# BMS_Rev1.net
KiCad netlist of a schematic drawn in EAGLE
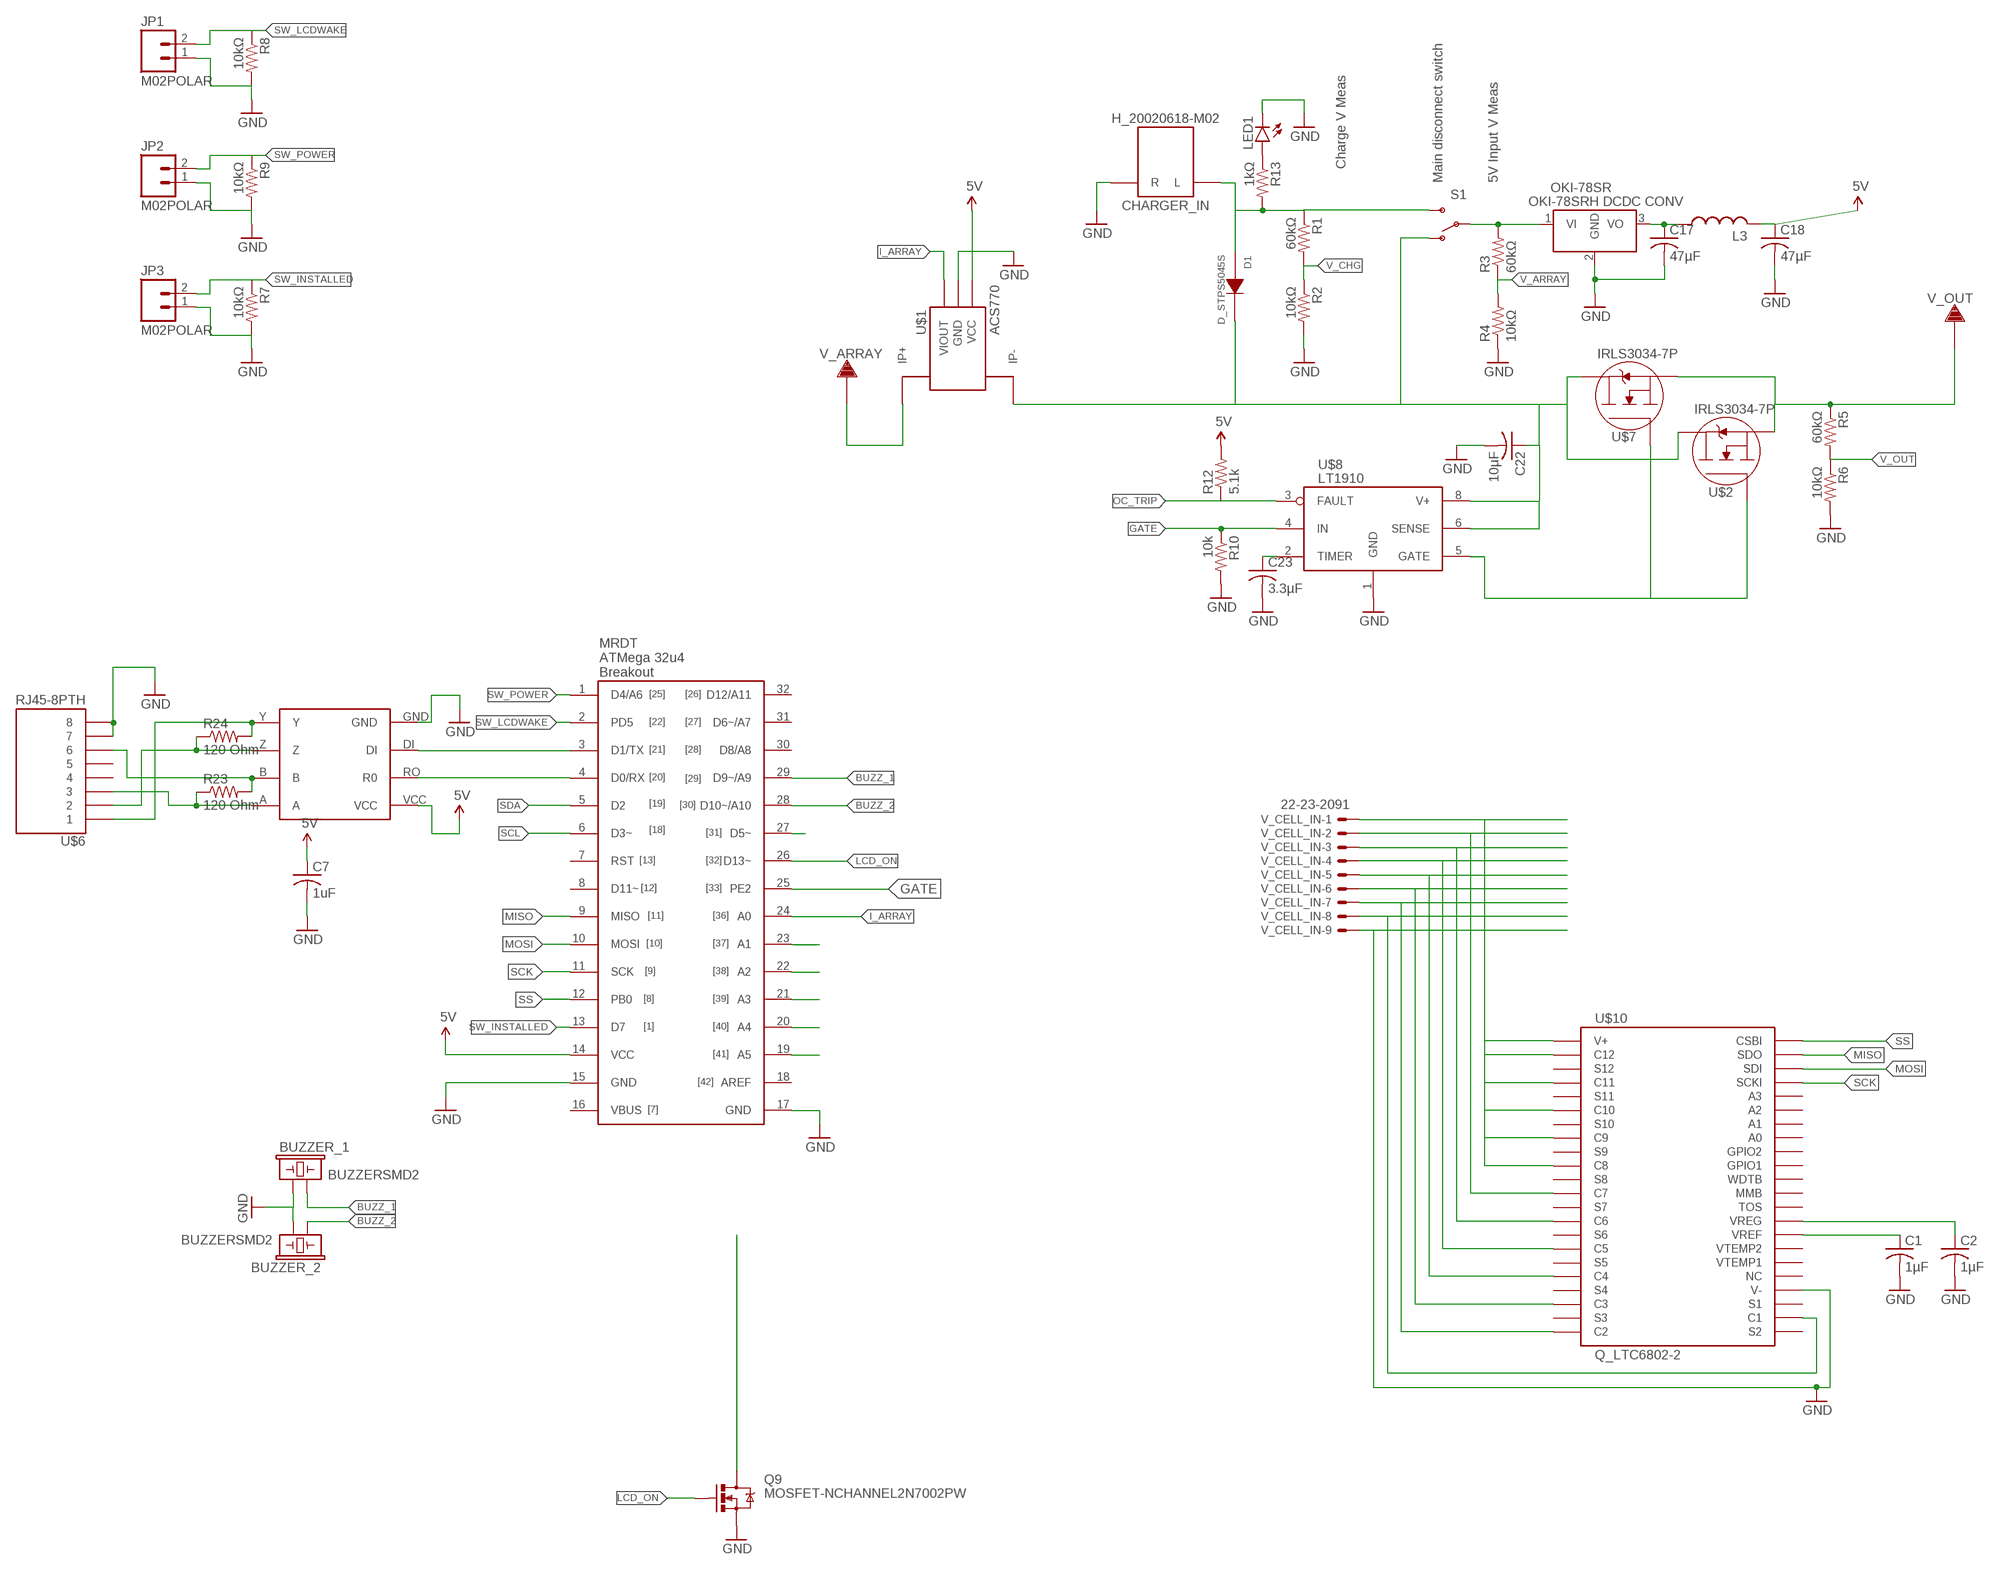
[diagram p0: schematic, sheet 1]

(export (version "E")
  (design (tool "Eeschema 10.0.6"))
  (components
    (comp (ref "BUZZER_1")
      (value "BUZZERSMD2")
      (footprint "eagle-import:BUZZER-CCV")
      (libsource (lib "eagle-import") (part "BUZZERSMD2"))
    )
    (comp (ref "BUZZER_2")
      (value "BUZZERSMD2")
      (footprint "eagle-import:BUZZER-CCV")
      (libsource (lib "eagle-import") (part "BUZZERSMD2"))
    )
    (comp (ref "C1")
      (value "1µF")
      (footprint "eagle-import:C1206")
      (libsource (lib "eagle-import") (part "C-USC1206"))
    )
    (comp (ref "C2")
      (value "1µF")
      (footprint "eagle-import:C1206")
      (libsource (lib "eagle-import") (part "C-USC1206"))
    )
    (comp (ref "C7")
      (value "1uF")
      (footprint "eagle-import:C1206")
      (libsource (lib "eagle-import") (part "C-USC1206"))
    )
    (comp (ref "C17")
      (value "47µF")
      (footprint "eagle-import:C1206")
      (libsource (lib "eagle-import") (part "C-USC1206"))
    )
    (comp (ref "C18")
      (value "47µF")
      (footprint "eagle-import:C1206")
      (libsource (lib "eagle-import") (part "C-USC1206"))
    )
    (comp (ref "C22")
      (value "10µF")
      (footprint "eagle-import:C1206")
      (libsource (lib "eagle-import") (part "C-USC1206"))
    )
    (comp (ref "C23")
      (value "3.3µF")
      (footprint "eagle-import:C1206")
      (libsource (lib "eagle-import") (part "C-USC1206"))
    )
    (comp (ref "CHARGER_IN")
      (value "H_20020618-M02")
      (footprint "eagle-import:20020618-M02")
      (libsource (lib "eagle-import") (part "H_20020618-M02"))
    )
    (comp (ref "D1")
      (value "D_STPS5045S")
      (footprint "eagle-import:D2PACK")
      (libsource (lib "eagle-import") (part "D_STPS5045S"))
    )
    (comp (ref "JP1")
      (value "M02POLAR")
      (footprint "eagle-import:MOLEX-1X2")
      (libsource (lib "eagle-import") (part "M02POLAR"))
    )
    (comp (ref "JP2")
      (value "M02POLAR")
      (footprint "eagle-import:MOLEX-1X2")
      (libsource (lib "eagle-import") (part "M02POLAR"))
    )
    (comp (ref "JP3")
      (value "M02POLAR")
      (footprint "eagle-import:MOLEX-1X2")
      (libsource (lib "eagle-import") (part "M02POLAR"))
    )
    (comp (ref "L3")
      (value "L-USL3216C")
      (footprint "eagle-import:L3216C")
      (libsource (lib "eagle-import") (part "L-USL3216C"))
    )
    (comp (ref "LED1")
      (value "LED1206")
      (footprint "eagle-import:LED-1206")
      (libsource (lib "eagle-import") (part "LED1206"))
    )
    (comp (ref "OKI-78SR")
      (value "Q_OKI-78SR")
      (footprint "eagle-import:OKI-78SRH")
      (libsource (lib "eagle-import") (part "Q_OKI-78SR"))
    )
    (comp (ref "Q9")
      (value "MOSFET-NCHANNEL2N7002PW")
      (footprint "eagle-import:SOT323")
      (libsource (lib "eagle-import") (part "MOSFET-NCHANNEL2N7002PW"))
    )
    (comp (ref "R1")
      (value "60kΩ")
      (footprint "eagle-import:R1206")
      (libsource (lib "eagle-import") (part "R-US_R1206"))
    )
    (comp (ref "R2")
      (value "10kΩ")
      (footprint "eagle-import:R1206")
      (libsource (lib "eagle-import") (part "R-US_R1206"))
    )
    (comp (ref "R3")
      (value "60kΩ")
      (footprint "eagle-import:R1206")
      (libsource (lib "eagle-import") (part "R-US_R1206"))
    )
    (comp (ref "R4")
      (value "10kΩ")
      (footprint "eagle-import:R1206")
      (libsource (lib "eagle-import") (part "R-US_R1206"))
    )
    (comp (ref "R5")
      (value "60kΩ")
      (footprint "eagle-import:R1206")
      (libsource (lib "eagle-import") (part "R-US_R1206"))
    )
    (comp (ref "R6")
      (value "10kΩ")
      (footprint "eagle-import:R1206")
      (libsource (lib "eagle-import") (part "R-US_R1206"))
    )
    (comp (ref "R7")
      (value "10kΩ")
      (footprint "eagle-import:R1206")
      (libsource (lib "eagle-import") (part "R-US_R1206"))
    )
    (comp (ref "R8")
      (value "10kΩ")
      (footprint "eagle-import:R1206")
      (libsource (lib "eagle-import") (part "R-US_R1206"))
    )
    (comp (ref "R9")
      (value "10kΩ")
      (footprint "eagle-import:R1206")
      (libsource (lib "eagle-import") (part "R-US_R1206"))
    )
    (comp (ref "R10")
      (value "10k")
      (footprint "eagle-import:R1206")
      (libsource (lib "eagle-import") (part "R-US_R1206"))
    )
    (comp (ref "R12")
      (value "5.1k")
      (footprint "eagle-import:R1206")
      (libsource (lib "eagle-import") (part "R-US_R1206"))
    )
    (comp (ref "R13")
      (value "1kΩ")
      (footprint "eagle-import:R1206")
      (libsource (lib "eagle-import") (part "R-US_R1206"))
    )
    (comp (ref "R23")
      (value "120 Ohm")
      (footprint "eagle-import:1206")
      (libsource (lib "eagle-import") (part "RESISTOR1206"))
    )
    (comp (ref "R24")
      (value "120 Ohm")
      (footprint "eagle-import:1206")
      (libsource (lib "eagle-import") (part "RESISTOR1206"))
    )
    (comp (ref "S1")
      (value "SWITCH-SPDTPTH")
      (footprint "eagle-import:SWITCH-SPDT")
      (libsource (lib "eagle-import") (part "SWITCH-SPDTPTH"))
    )
    (comp (ref "U$1")
      (value "ACS770")
      (footprint "eagle-import:PFF_LEADFORM")
      (libsource (lib "eagle-import") (part "ACS770"))
    )
    (comp (ref "U$2")
      (value "IRLS3034-7P")
      (footprint "eagle-import:D2PAK-7")
      (libsource (lib "eagle-import") (part "IRLS3034-7P"))
    )
    (comp (ref "U$3")
      (value "32U4_BREAKOUT")
      (footprint "eagle-import:32U4_MCU_DIP")
      (libsource (lib "eagle-import") (part "32U4_BREAKOUT"))
    )
    (comp (ref "U$6")
      (value "RJ45-8PTH")
      (footprint "eagle-import:RJ45-8")
      (libsource (lib "eagle-import") (part "RJ45-8PTH"))
    )
    (comp (ref "U$7")
      (value "IRLS3034-7P")
      (footprint "eagle-import:D2PAK-7")
      (libsource (lib "eagle-import") (part "IRLS3034-7P"))
    )
    (comp (ref "U$8")
      (value "LT1910")
      (footprint "eagle-import:SO8")
      (libsource (lib "eagle-import") (part "LT1910"))
    )
    (comp (ref "U$9")
      (value "MAX3077")
      (footprint "eagle-import:MAX3070E")
      (libsource (lib "eagle-import") (part "MAX3077"))
    )
    (comp (ref "U$10")
      (value "Q_LTC6802-2")
      (footprint "eagle-import:SSOP44")
      (libsource (lib "eagle-import") (part "Q_LTC6802-2"))
    )
    (comp (ref "V_ARRAY")
      (value "TERMINAL_HOLE")
      (footprint "eagle-import:LARGE_TERMINAL_HOLE")
      (libsource (lib "eagle-import") (part "TERMINAL_HOLE"))
    )
    (comp (ref "V_CELL_IN")
      (value "22-23-2091")
      (footprint "eagle-import:22-23-2091")
      (fields (field (name "MF") "MOLEX"))
      (libsource (lib "eagle-import") (part "22-23-2091"))
    )
    (comp (ref "V_OUT")
      (value "TERMINAL_HOLE")
      (footprint "eagle-import:LARGE_TERMINAL_HOLE")
      (libsource (lib "eagle-import") (part "TERMINAL_HOLE"))
    )
  )
  (nets
    (net (code "1") (name "5V") (class "Default")
      (node (ref "C18") (pin "1") (pinfunction "1_1") (pintype "passive"))
      (node (ref "C7") (pin "1") (pinfunction "1_1") (pintype "passive"))
      (node (ref "L3") (pin "2") (pinfunction "2_2") (pintype "passive"))
      (node (ref "R12") (pin "2") (pinfunction "2_2") (pintype "passive"))
      (node (ref "U$1") (pin "1") (pinfunction "VCC_1") (pintype "bidirectional"))
      (node (ref "U$3") (pin "14") (pinfunction "VCC_14") (pintype "bidirectional"))
      (node (ref "U$9") (pin "VCC") (pinfunction "VCC_VCC") (pintype "bidirectional"))
    )
    (net (code "2") (name "BUZZ_1") (class "Default")
      (node (ref "BUZZER_1") (pin "-") (pinfunction "2_-") (pintype "passive"))
      (node (ref "U$3") (pin "29") (pinfunction "D9~{/A9}_29") (pintype "bidirectional"))
    )
    (net (code "3") (name "BUZZ_2") (class "Default")
      (node (ref "BUZZER_2") (pin "+") (pinfunction "1_+") (pintype "passive"))
      (node (ref "U$3") (pin "28") (pinfunction "D10~{/A10}_28") (pintype "bidirectional"))
    )
    (net (code "4") (name "GATE") (class "Default")
      (node (ref "R10") (pin "1") (pinfunction "1_1") (pintype "passive"))
      (node (ref "U$3") (pin "25") (pinfunction "PE2_25") (pintype "bidirectional"))
      (node (ref "U$8") (pin "4") (pinfunction "IN_4") (pintype "bidirectional"))
    )
    (net (code "5") (name "GND") (class "Default")
      (node (ref "BUZZER_1") (pin "+") (pinfunction "1_+") (pintype "passive"))
      (node (ref "BUZZER_2") (pin "-") (pinfunction "2_-") (pintype "passive"))
      (node (ref "C1") (pin "2") (pinfunction "2_2") (pintype "passive"))
      (node (ref "C17") (pin "2") (pinfunction "2_2") (pintype "passive"))
      (node (ref "C18") (pin "2") (pinfunction "2_2") (pintype "passive"))
      (node (ref "C2") (pin "2") (pinfunction "2_2") (pintype "passive"))
      (node (ref "C22") (pin "2") (pinfunction "2_2") (pintype "passive"))
      (node (ref "C23") (pin "2") (pinfunction "2_2") (pintype "passive"))
      (node (ref "C7") (pin "2") (pinfunction "2_2") (pintype "passive"))
      (node (ref "CHARGER_IN") (pin "R1") (pinfunction "R_R1") (pintype "bidirectional"))
      (node (ref "CHARGER_IN") (pin "R2") (pinfunction "R_R2") (pintype "bidirectional"))
      (node (ref "JP1") (pin "1") (pinfunction "1_1") (pintype "passive"))
      (node (ref "JP2") (pin "1") (pinfunction "1_1") (pintype "passive"))
      (node (ref "JP3") (pin "1") (pinfunction "1_1") (pintype "passive"))
      (node (ref "LED1") (pin "C") (pinfunction "C_C") (pintype "passive"))
      (node (ref "OKI-78SR") (pin "2") (pinfunction "GND_2") (pintype "bidirectional"))
      (node (ref "Q9") (pin "2") (pinfunction "S_2") (pintype "passive"))
      (node (ref "R10") (pin "2") (pinfunction "2_2") (pintype "passive"))
      (node (ref "R2") (pin "2") (pinfunction "2_2") (pintype "passive"))
      (node (ref "R4") (pin "1") (pinfunction "1_1") (pintype "passive"))
      (node (ref "R6") (pin "2") (pinfunction "2_2") (pintype "passive"))
      (node (ref "R7") (pin "2") (pinfunction "2_2") (pintype "passive"))
      (node (ref "R8") (pin "2") (pinfunction "2_2") (pintype "passive"))
      (node (ref "R9") (pin "2") (pinfunction "2_2") (pintype "passive"))
      (node (ref "U$1") (pin "2") (pinfunction "GND_2") (pintype "bidirectional"))
      (node (ref "U$10") (pin "26") (pinfunction "V-_26") (pintype "bidirectional"))
      (node (ref "U$3") (pin "15") (pinfunction "GND_15") (pintype "bidirectional"))
      (node (ref "U$3") (pin "17") (pinfunction "GND_17") (pintype "bidirectional"))
      (node (ref "U$6") (pin "7") (pinfunction "7_7") (pintype "bidirectional"))
      (node (ref "U$6") (pin "8") (pinfunction "8_8") (pintype "bidirectional"))
      (node (ref "U$8") (pin "1") (pinfunction "GND_1") (pintype "bidirectional"))
      (node (ref "U$9") (pin "GND") (pinfunction "GND_GND") (pintype "bidirectional"))
      (node (ref "V_CELL_IN") (pin "9") (pinfunction "S_9") (pintype "passive"))
    )
    (net (code "6") (name "I_ARRAY") (class "Default")
      (node (ref "U$1") (pin "3") (pinfunction "VIOUT_3") (pintype "bidirectional"))
      (node (ref "U$3") (pin "24") (pinfunction "A0_24") (pintype "bidirectional"))
    )
    (net (code "7") (name "LCD_ON") (class "Default")
      (node (ref "Q9") (pin "1") (pinfunction "G_1") (pintype "passive"))
      (node (ref "U$3") (pin "26") (pinfunction "D13~{}_26") (pintype "bidirectional"))
    )
    (net (code "8") (name "MISO") (class "Default")
      (node (ref "U$10") (pin "43") (pinfunction "SDO_43") (pintype "bidirectional"))
      (node (ref "U$3") (pin "9") (pinfunction "MISO_9") (pintype "bidirectional"))
    )
    (net (code "9") (name "MOSI") (class "Default")
      (node (ref "U$10") (pin "42") (pinfunction "SDI_42") (pintype "bidirectional"))
      (node (ref "U$3") (pin "10") (pinfunction "MOSI_10") (pintype "bidirectional"))
    )
    (net (code "10") (name "Net-(D1-K)") (class "Default")
      (node (ref "C22") (pin "1") (pinfunction "1_1") (pintype "passive"))
      (node (ref "D1") (pin "TAB") (pinfunction "K_TAB") (pintype "bidirectional"))
      (node (ref "S1") (pin "1") (pinfunction "O_1") (pintype "passive"))
      (node (ref "U$1") (pin "5_1") (pinfunction "IP-_5_1") (pintype "bidirectional"))
      (node (ref "U$1") (pin "5_10") (pinfunction "IP-_5_10") (pintype "bidirectional"))
      (node (ref "U$1") (pin "5_11") (pinfunction "IP-_5_11") (pintype "bidirectional"))
      (node (ref "U$1") (pin "5_12") (pinfunction "IP-_5_12") (pintype "bidirectional"))
      (node (ref "U$1") (pin "5_13") (pinfunction "IP-_5_13") (pintype "bidirectional"))
      (node (ref "U$1") (pin "5_14") (pinfunction "IP-_5_14") (pintype "bidirectional"))
      (node (ref "U$1") (pin "5_15") (pinfunction "IP-_5_15") (pintype "bidirectional"))
      (node (ref "U$1") (pin "5_16") (pinfunction "IP-_5_16") (pintype "bidirectional"))
      (node (ref "U$1") (pin "5_2") (pinfunction "IP-_5_2") (pintype "bidirectional"))
      (node (ref "U$1") (pin "5_3") (pinfunction "IP-_5_3") (pintype "bidirectional"))
      (node (ref "U$1") (pin "5_4") (pinfunction "IP-_5_4") (pintype "bidirectional"))
      (node (ref "U$1") (pin "5_5") (pinfunction "IP-_5_5") (pintype "bidirectional"))
      (node (ref "U$1") (pin "5_6") (pinfunction "IP-_5_6") (pintype "bidirectional"))
      (node (ref "U$1") (pin "5_7") (pinfunction "IP-_5_7") (pintype "bidirectional"))
      (node (ref "U$1") (pin "5_8") (pinfunction "IP-_5_8") (pintype "bidirectional"))
      (node (ref "U$1") (pin "5_9") (pinfunction "IP-_5_9") (pintype "bidirectional"))
      (node (ref "U$1") (pin "5_B") (pinfunction "IP-_5_B") (pintype "bidirectional"))
      (node (ref "U$1") (pin "5_T") (pinfunction "IP-_5_T") (pintype "bidirectional"))
      (node (ref "U$2") (pin "PAD") (pinfunction "DRAIN_PAD") (pintype "bidirectional"))
      (node (ref "U$7") (pin "PAD") (pinfunction "DRAIN_PAD") (pintype "bidirectional"))
      (node (ref "U$8") (pin "6") (pinfunction "SENSE_6") (pintype "bidirectional"))
      (node (ref "U$8") (pin "8") (pinfunction "V+_8") (pintype "bidirectional"))
    )
    (net (code "11") (name "Net-(LED1-PadA)") (class "Default")
      (node (ref "LED1") (pin "A") (pinfunction "A_A") (pintype "passive"))
      (node (ref "R13") (pin "1") (pinfunction "1_1") (pintype "passive"))
    )
    (net (code "12") (name "Net-(OKI-78SR-VI)") (class "Default")
      (node (ref "OKI-78SR") (pin "1") (pinfunction "VI_1") (pintype "bidirectional"))
      (node (ref "R3") (pin "2") (pinfunction "2_2") (pintype "passive"))
      (node (ref "S1") (pin "2") (pinfunction "P_2") (pintype "passive"))
    )
    (net (code "13") (name "Net-(OKI-78SR-VO)") (class "Default")
      (node (ref "C17") (pin "1") (pinfunction "1_1") (pintype "passive"))
      (node (ref "L3") (pin "1") (pinfunction "1_1") (pintype "passive"))
      (node (ref "OKI-78SR") (pin "3") (pinfunction "VO_3") (pintype "bidirectional"))
    )
    (net (code "14") (name "Net-(R5-Pad1)") (class "Default")
      (node (ref "R5") (pin "1") (pinfunction "1_1") (pintype "passive"))
      (node (ref "U$2") (pin "2") (pinfunction "SOURCE_2") (pintype "bidirectional"))
      (node (ref "U$2") (pin "3") (pinfunction "SOURCE_3") (pintype "bidirectional"))
      (node (ref "U$2") (pin "4") (pinfunction "SOURCE_4") (pintype "bidirectional"))
      (node (ref "U$2") (pin "5") (pinfunction "SOURCE_5") (pintype "bidirectional"))
      (node (ref "U$2") (pin "6") (pinfunction "SOURCE_6") (pintype "bidirectional"))
      (node (ref "U$7") (pin "2") (pinfunction "SOURCE_2") (pintype "bidirectional"))
      (node (ref "U$7") (pin "3") (pinfunction "SOURCE_3") (pintype "bidirectional"))
      (node (ref "U$7") (pin "4") (pinfunction "SOURCE_4") (pintype "bidirectional"))
      (node (ref "U$7") (pin "5") (pinfunction "SOURCE_5") (pintype "bidirectional"))
      (node (ref "U$7") (pin "6") (pinfunction "SOURCE_6") (pintype "bidirectional"))
      (node (ref "V_OUT") (pin "P$1") (pinfunction "P$1_P$1") (pintype "bidirectional"))
    )
    (net (code "15") (name "Net-(R23-Pad1)") (class "Default")
      (node (ref "R23") (pin "1") (pinfunction "1_1") (pintype "passive"))
      (node (ref "U$6") (pin "3") (pinfunction "3_3") (pintype "bidirectional"))
      (node (ref "U$9") (pin "A") (pinfunction "A_A") (pintype "bidirectional"))
    )
    (net (code "16") (name "Net-(R23-Pad2)") (class "Default")
      (node (ref "R23") (pin "2") (pinfunction "2_2") (pintype "passive"))
      (node (ref "U$6") (pin "6") (pinfunction "6_6") (pintype "bidirectional"))
      (node (ref "U$9") (pin "B") (pinfunction "B_B") (pintype "bidirectional"))
    )
    (net (code "17") (name "Net-(R24-Pad1)") (class "Default")
      (node (ref "R24") (pin "1") (pinfunction "1_1") (pintype "passive"))
      (node (ref "U$6") (pin "2") (pinfunction "2_2") (pintype "bidirectional"))
      (node (ref "U$9") (pin "Z") (pinfunction "Z_Z") (pintype "bidirectional"))
    )
    (net (code "18") (name "Net-(R24-Pad2)") (class "Default")
      (node (ref "R24") (pin "2") (pinfunction "2_2") (pintype "passive"))
      (node (ref "U$6") (pin "1") (pinfunction "1_1") (pintype "bidirectional"))
      (node (ref "U$9") (pin "Y") (pinfunction "Y_Y") (pintype "bidirectional"))
    )
    (net (code "19") (name "Net-(S1-S)") (class "Default")
      (node (ref "CHARGER_IN") (pin "L1") (pinfunction "L_L1") (pintype "bidirectional"))
      (node (ref "CHARGER_IN") (pin "L2") (pinfunction "L_L2") (pintype "bidirectional"))
      (node (ref "D1") (pin "1") (pinfunction "A_1") (pintype "bidirectional"))
      (node (ref "D1") (pin "2") (pinfunction "A_2") (pintype "bidirectional"))
      (node (ref "R1") (pin "1") (pinfunction "1_1") (pintype "passive"))
      (node (ref "R13") (pin "2") (pinfunction "2_2") (pintype "passive"))
      (node (ref "S1") (pin "3") (pinfunction "S_3") (pintype "passive"))
    )
    (net (code "20") (name "Net-(U$1-IP+-Pad4_1)") (class "Default")
      (node (ref "U$1") (pin "4_1") (pinfunction "IP+_4_1") (pintype "bidirectional"))
      (node (ref "U$1") (pin "4_10") (pinfunction "IP+_4_10") (pintype "bidirectional"))
      (node (ref "U$1") (pin "4_11") (pinfunction "IP+_4_11") (pintype "bidirectional"))
      (node (ref "U$1") (pin "4_12") (pinfunction "IP+_4_12") (pintype "bidirectional"))
      (node (ref "U$1") (pin "4_13") (pinfunction "IP+_4_13") (pintype "bidirectional"))
      (node (ref "U$1") (pin "4_14") (pinfunction "IP+_4_14") (pintype "bidirectional"))
      (node (ref "U$1") (pin "4_15") (pinfunction "IP+_4_15") (pintype "bidirectional"))
      (node (ref "U$1") (pin "4_16") (pinfunction "IP+_4_16") (pintype "bidirectional"))
      (node (ref "U$1") (pin "4_2") (pinfunction "IP+_4_2") (pintype "bidirectional"))
      (node (ref "U$1") (pin "4_3") (pinfunction "IP+_4_3") (pintype "bidirectional"))
      (node (ref "U$1") (pin "4_4") (pinfunction "IP+_4_4") (pintype "bidirectional"))
      (node (ref "U$1") (pin "4_5") (pinfunction "IP+_4_5") (pintype "bidirectional"))
      (node (ref "U$1") (pin "4_6") (pinfunction "IP+_4_6") (pintype "bidirectional"))
      (node (ref "U$1") (pin "4_7") (pinfunction "IP+_4_7") (pintype "bidirectional"))
      (node (ref "U$1") (pin "4_8") (pinfunction "IP+_4_8") (pintype "bidirectional"))
      (node (ref "U$1") (pin "4_9") (pinfunction "IP+_4_9") (pintype "bidirectional"))
      (node (ref "U$1") (pin "4_B") (pinfunction "IP+_4_B") (pintype "bidirectional"))
      (node (ref "U$1") (pin "4_T") (pinfunction "IP+_4_T") (pintype "bidirectional"))
      (node (ref "V_ARRAY") (pin "P$1") (pinfunction "P$1_P$1") (pintype "bidirectional"))
    )
    (net (code "21") (name "Net-(U$2-GATE)") (class "Default")
      (node (ref "U$2") (pin "1") (pinfunction "GATE_1") (pintype "bidirectional"))
      (node (ref "U$7") (pin "1") (pinfunction "GATE_1") (pintype "bidirectional"))
      (node (ref "U$8") (pin "5") (pinfunction "GATE_5") (pintype "bidirectional"))
    )
    (net (code "22") (name "Net-(U$3-D0{slash}RX)") (class "Default")
      (node (ref "U$3") (pin "4") (pinfunction "D0/RX_4") (pintype "bidirectional"))
      (node (ref "U$9") (pin "RO") (pinfunction "R0_RO") (pintype "bidirectional"))
    )
    (net (code "23") (name "Net-(U$3-D1{slash}TX)") (class "Default")
      (node (ref "U$3") (pin "3") (pinfunction "D1/TX_3") (pintype "bidirectional"))
      (node (ref "U$9") (pin "DI") (pinfunction "DI_DI") (pintype "bidirectional"))
    )
    (net (code "24") (name "Net-(U$8-TIMER)") (class "Default")
      (node (ref "C23") (pin "1") (pinfunction "1_1") (pintype "passive"))
      (node (ref "U$8") (pin "2") (pinfunction "TIMER_2") (pintype "bidirectional"))
    )
    (net (code "25") (name "Net-(U$10-C1)") (class "Default")
      (node (ref "U$10") (pin "24") (pinfunction "C1_24") (pintype "bidirectional"))
      (node (ref "V_CELL_IN") (pin "8") (pinfunction "S_8") (pintype "passive"))
    )
    (net (code "26") (name "Net-(U$10-C2)") (class "Default")
      (node (ref "U$10") (pin "22") (pinfunction "C2_22") (pintype "bidirectional"))
      (node (ref "V_CELL_IN") (pin "7") (pinfunction "S_7") (pintype "passive"))
    )
    (net (code "27") (name "Net-(U$10-C3)") (class "Default")
      (node (ref "U$10") (pin "20") (pinfunction "C3_20") (pintype "bidirectional"))
      (node (ref "V_CELL_IN") (pin "6") (pinfunction "S_6") (pintype "passive"))
    )
    (net (code "28") (name "Net-(U$10-C4)") (class "Default")
      (node (ref "U$10") (pin "18") (pinfunction "C4_18") (pintype "bidirectional"))
      (node (ref "V_CELL_IN") (pin "5") (pinfunction "S_5") (pintype "passive"))
    )
    (net (code "29") (name "Net-(U$10-C5)") (class "Default")
      (node (ref "U$10") (pin "16") (pinfunction "C5_16") (pintype "bidirectional"))
      (node (ref "V_CELL_IN") (pin "4") (pinfunction "S_4") (pintype "passive"))
    )
    (net (code "30") (name "Net-(U$10-C6)") (class "Default")
      (node (ref "U$10") (pin "14") (pinfunction "C6_14") (pintype "bidirectional"))
      (node (ref "V_CELL_IN") (pin "3") (pinfunction "S_3") (pintype "passive"))
    )
    (net (code "31") (name "Net-(U$10-C7)") (class "Default")
      (node (ref "U$10") (pin "12") (pinfunction "C7_12") (pintype "bidirectional"))
      (node (ref "V_CELL_IN") (pin "2") (pinfunction "S_2") (pintype "passive"))
    )
    (net (code "32") (name "Net-(U$10-C10)") (class "Default")
      (node (ref "U$10") (pin "1") (pinfunction "V+_1") (pintype "bidirectional"))
      (node (ref "U$10") (pin "10") (pinfunction "C8_10") (pintype "bidirectional"))
      (node (ref "U$10") (pin "2") (pinfunction "C12_2") (pintype "bidirectional"))
      (node (ref "U$10") (pin "4") (pinfunction "C11_4") (pintype "bidirectional"))
      (node (ref "U$10") (pin "6") (pinfunction "C10_6") (pintype "bidirectional"))
      (node (ref "U$10") (pin "8") (pinfunction "C9_8") (pintype "bidirectional"))
      (node (ref "V_CELL_IN") (pin "1") (pinfunction "S_1") (pintype "passive"))
    )
    (net (code "33") (name "Net-(U$10-VREF)") (class "Default")
      (node (ref "C1") (pin "1") (pinfunction "1_1") (pintype "passive"))
      (node (ref "U$10") (pin "30") (pinfunction "VREF_30") (pintype "bidirectional"))
    )
    (net (code "34") (name "Net-(U$10-VREG)") (class "Default")
      (node (ref "C2") (pin "1") (pinfunction "1_1") (pintype "passive"))
      (node (ref "U$10") (pin "31") (pinfunction "VREG_31") (pintype "bidirectional"))
    )
    (net (code "35") (name "OC_TRIP") (class "Default")
      (node (ref "R12") (pin "1") (pinfunction "1_1") (pintype "passive"))
      (node (ref "U$8") (pin "3") (pinfunction "FAULT_3") (pintype "bidirectional"))
    )
    (net (code "36") (name "SCK") (class "Default")
      (node (ref "U$10") (pin "41") (pinfunction "SCKI_41") (pintype "bidirectional"))
      (node (ref "U$3") (pin "11") (pinfunction "SCK_11") (pintype "bidirectional"))
    )
    (net (code "37") (name "SCL") (class "Default")
      (node (ref "U$3") (pin "6") (pinfunction "D3~{}_6") (pintype "bidirectional"))
    )
    (net (code "38") (name "SDA") (class "Default")
      (node (ref "U$3") (pin "5") (pinfunction "D2_5") (pintype "bidirectional"))
    )
    (net (code "39") (name "SS") (class "Default")
      (node (ref "U$10") (pin "44") (pinfunction "CSBI_44") (pintype "bidirectional"))
      (node (ref "U$3") (pin "12") (pinfunction "PB0_12") (pintype "bidirectional"))
    )
    (net (code "40") (name "SW_INSTALLED") (class "Default")
      (node (ref "JP3") (pin "2") (pinfunction "2_2") (pintype "passive"))
      (node (ref "R7") (pin "1") (pinfunction "1_1") (pintype "passive"))
      (node (ref "U$3") (pin "13") (pinfunction "D7_13") (pintype "bidirectional"))
    )
    (net (code "41") (name "SW_LCDWAKE") (class "Default")
      (node (ref "JP1") (pin "2") (pinfunction "2_2") (pintype "passive"))
      (node (ref "R8") (pin "1") (pinfunction "1_1") (pintype "passive"))
      (node (ref "U$3") (pin "2") (pinfunction "PD5_2") (pintype "bidirectional"))
    )
    (net (code "42") (name "SW_POWER") (class "Default")
      (node (ref "JP2") (pin "2") (pinfunction "2_2") (pintype "passive"))
      (node (ref "R9") (pin "1") (pinfunction "1_1") (pintype "passive"))
      (node (ref "U$3") (pin "1") (pinfunction "D4/A6_1") (pintype "bidirectional"))
    )
    (net (code "43") (name "V_ARRAY") (class "Default")
      (node (ref "R3") (pin "1") (pinfunction "1_1") (pintype "passive"))
      (node (ref "R4") (pin "2") (pinfunction "2_2") (pintype "passive"))
    )
    (net (code "44") (name "V_CHG") (class "Default")
      (node (ref "R1") (pin "2") (pinfunction "2_2") (pintype "passive"))
      (node (ref "R2") (pin "1") (pinfunction "1_1") (pintype "passive"))
    )
    (net (code "45") (name "V_OUT") (class "Default")
      (node (ref "R5") (pin "2") (pinfunction "2_2") (pintype "passive"))
      (node (ref "R6") (pin "1") (pinfunction "1_1") (pintype "passive"))
    )
    (net (code "46") (name "unconnected-(Q9-D-Pad3)") (class "Default")
      (node (ref "Q9") (pin "3") (pinfunction "D_3") (pintype "passive"))
    )
    (net (code "47") (name "unconnected-(U$3-A1-Pad23)") (class "Default")
      (node (ref "U$3") (pin "23") (pinfunction "A1_23") (pintype "bidirectional"))
    )
    (net (code "48") (name "unconnected-(U$3-A2-Pad22)") (class "Default")
      (node (ref "U$3") (pin "22") (pinfunction "A2_22") (pintype "bidirectional"))
    )
    (net (code "49") (name "unconnected-(U$3-A3-Pad21)") (class "Default")
      (node (ref "U$3") (pin "21") (pinfunction "A3_21") (pintype "bidirectional"))
    )
    (net (code "50") (name "unconnected-(U$3-A4-Pad20)") (class "Default")
      (node (ref "U$3") (pin "20") (pinfunction "A4_20") (pintype "bidirectional"))
    )
    (net (code "51") (name "unconnected-(U$3-A5-Pad19)") (class "Default")
      (node (ref "U$3") (pin "19") (pinfunction "A5_19") (pintype "bidirectional"))
    )
    (net (code "52") (name "unconnected-(U$3-AREF-Pad18)") (class "Default")
      (node (ref "U$3") (pin "18") (pinfunction "AREF_18") (pintype "bidirectional"))
    )
    (net (code "53") (name "unconnected-(U$3-D5~{}-Pad27)") (class "Default")
      (node (ref "U$3") (pin "27") (pinfunction "D5~{}_27") (pintype "bidirectional"))
    )
    (net (code "54") (name "unconnected-(U$3-D6~{{slash}A7}-Pad31)") (class "Default")
      (node (ref "U$3") (pin "31") (pinfunction "D6~{/A7}_31") (pintype "bidirectional"))
    )
    (net (code "55") (name "unconnected-(U$3-D8{slash}A8-Pad30)") (class "Default")
      (node (ref "U$3") (pin "30") (pinfunction "D8/A8_30") (pintype "bidirectional"))
    )
    (net (code "56") (name "unconnected-(U$3-D11~{}-Pad8)") (class "Default")
      (node (ref "U$3") (pin "8") (pinfunction "D11~{}_8") (pintype "bidirectional"))
    )
    (net (code "57") (name "unconnected-(U$3-D12{slash}A11-Pad32)") (class "Default")
      (node (ref "U$3") (pin "32") (pinfunction "D12/A11_32") (pintype "bidirectional"))
    )
    (net (code "58") (name "unconnected-(U$3-RST-Pad7)") (class "Default")
      (node (ref "U$3") (pin "7") (pinfunction "RST_7") (pintype "bidirectional"))
    )
    (net (code "59") (name "unconnected-(U$3-VBUS-Pad16)") (class "Default")
      (node (ref "U$3") (pin "16") (pinfunction "VBUS_16") (pintype "bidirectional"))
    )
    (net (code "60") (name "unconnected-(U$6-Pad4)") (class "Default")
      (node (ref "U$6") (pin "4") (pinfunction "4_4") (pintype "bidirectional"))
    )
    (net (code "61") (name "unconnected-(U$6-Pad5)") (class "Default")
      (node (ref "U$6") (pin "5") (pinfunction "5_5") (pintype "bidirectional"))
    )
    (net (code "62") (name "unconnected-(U$10-A0-Pad37)") (class "Default")
      (node (ref "U$10") (pin "37") (pinfunction "A0_37") (pintype "bidirectional"))
    )
    (net (code "63") (name "unconnected-(U$10-A1-Pad38)") (class "Default")
      (node (ref "U$10") (pin "38") (pinfunction "A1_38") (pintype "bidirectional"))
    )
    (net (code "64") (name "unconnected-(U$10-A2-Pad39)") (class "Default")
      (node (ref "U$10") (pin "39") (pinfunction "A2_39") (pintype "bidirectional"))
    )
    (net (code "65") (name "unconnected-(U$10-A3-Pad40)") (class "Default")
      (node (ref "U$10") (pin "40") (pinfunction "A3_40") (pintype "bidirectional"))
    )
    (net (code "66") (name "unconnected-(U$10-GPIO1-Pad35)") (class "Default")
      (node (ref "U$10") (pin "35") (pinfunction "GPIO1_35") (pintype "bidirectional"))
    )
    (net (code "67") (name "unconnected-(U$10-GPIO2-Pad36)") (class "Default")
      (node (ref "U$10") (pin "36") (pinfunction "GPIO2_36") (pintype "bidirectional"))
    )
    (net (code "68") (name "unconnected-(U$10-MMB-Pad33)") (class "Default")
      (node (ref "U$10") (pin "33") (pinfunction "MMB_33") (pintype "bidirectional"))
    )
    (net (code "69") (name "unconnected-(U$10-NC-Pad27)") (class "Default")
      (node (ref "U$10") (pin "27") (pinfunction "NC_27") (pintype "bidirectional"))
    )
    (net (code "70") (name "unconnected-(U$10-S1-Pad25)") (class "Default")
      (node (ref "U$10") (pin "25") (pinfunction "S1_25") (pintype "bidirectional"))
    )
    (net (code "71") (name "unconnected-(U$10-S2-Pad23)") (class "Default")
      (node (ref "U$10") (pin "23") (pinfunction "S2_23") (pintype "bidirectional"))
    )
    (net (code "72") (name "unconnected-(U$10-S3-Pad21)") (class "Default")
      (node (ref "U$10") (pin "21") (pinfunction "S3_21") (pintype "bidirectional"))
    )
    (net (code "73") (name "unconnected-(U$10-S4-Pad19)") (class "Default")
      (node (ref "U$10") (pin "19") (pinfunction "S4_19") (pintype "bidirectional"))
    )
    (net (code "74") (name "unconnected-(U$10-S5-Pad17)") (class "Default")
      (node (ref "U$10") (pin "17") (pinfunction "S5_17") (pintype "bidirectional"))
    )
    (net (code "75") (name "unconnected-(U$10-S6-Pad15)") (class "Default")
      (node (ref "U$10") (pin "15") (pinfunction "S6_15") (pintype "bidirectional"))
    )
    (net (code "76") (name "unconnected-(U$10-S7-Pad13)") (class "Default")
      (node (ref "U$10") (pin "13") (pinfunction "S7_13") (pintype "bidirectional"))
    )
    (net (code "77") (name "unconnected-(U$10-S8-Pad11)") (class "Default")
      (node (ref "U$10") (pin "11") (pinfunction "S8_11") (pintype "bidirectional"))
    )
    (net (code "78") (name "unconnected-(U$10-S9-Pad9)") (class "Default")
      (node (ref "U$10") (pin "9") (pinfunction "S9_9") (pintype "bidirectional"))
    )
    (net (code "79") (name "unconnected-(U$10-S10-Pad7)") (class "Default")
      (node (ref "U$10") (pin "7") (pinfunction "S10_7") (pintype "bidirectional"))
    )
    (net (code "80") (name "unconnected-(U$10-S11-Pad5)") (class "Default")
      (node (ref "U$10") (pin "5") (pinfunction "S11_5") (pintype "bidirectional"))
    )
    (net (code "81") (name "unconnected-(U$10-S12-Pad3)") (class "Default")
      (node (ref "U$10") (pin "3") (pinfunction "S12_3") (pintype "bidirectional"))
    )
    (net (code "82") (name "unconnected-(U$10-TOS-Pad32)") (class "Default")
      (node (ref "U$10") (pin "32") (pinfunction "TOS_32") (pintype "bidirectional"))
    )
    (net (code "83") (name "unconnected-(U$10-VTEMP1-Pad28)") (class "Default")
      (node (ref "U$10") (pin "28") (pinfunction "VTEMP1_28") (pintype "bidirectional"))
    )
    (net (code "84") (name "unconnected-(U$10-VTEMP2-Pad29)") (class "Default")
      (node (ref "U$10") (pin "29") (pinfunction "VTEMP2_29") (pintype "bidirectional"))
    )
    (net (code "85") (name "unconnected-(U$10-WDTB-Pad34)") (class "Default")
      (node (ref "U$10") (pin "34") (pinfunction "WDTB_34") (pintype "bidirectional"))
    )
  )
)
